# BackscatterPlantSensor_v2_test2.net
KiCad netlist of a schematic drawn in EAGLE
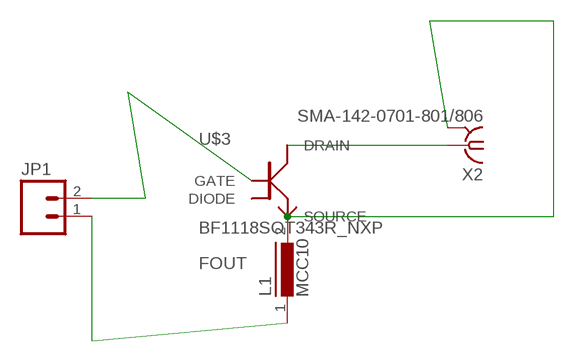
[diagram p0: schematic, sheet 1]

(export (version "E")
  (design (tool "Eeschema 10.0.6"))
  (components
    (comp (ref "JP1")
      (value "M02PTH")
      (footprint "eagle-import:1X02")
      (libsource (lib "eagle-import") (part "M02PTH"))
    )
    (comp (ref "L1")
      (value "MCC10")
      (footprint "eagle-import:MCC10")
      (libsource (lib "eagle-import") (part "MCC10"))
    )
    (comp (ref "U$3")
      (value "BF1118SOT343R_NXP")
      (footprint "eagle-import:SOT343R")
      (libsource (lib "eagle-import") (part "BF1118SOT343R_NXP"))
    )
    (comp (ref "X2")
      (value "SMA-142-0701-801/806")
      (footprint "eagle-import:J502-ND-142-0701-801_806")
      (fields (field (name "MF") "JOHNSON COMPONENTS") (field (name "MPN") "142-0701-801"))
      (libsource (lib "eagle-import") (part "SMA-142-0701-801/806"))
    )
  )
  (nets
    (net (code "1") (name "FOUT") (class "Default")
      (node (ref "JP1") (pin "1") (pinfunction "1_1") (pintype "passive"))
      (node (ref "L1") (pin "1") (pinfunction "1_1") (pintype "passive"))
    )
    (net (code "2") (name "Net-(U$3-DRAIN)") (class "Default")
      (node (ref "U$3") (pin "4") (pinfunction "DRAIN_4") (pintype "bidirectional"))
      (node (ref "X2") (pin "1") (pinfunction "1_1") (pintype "passive"))
    )
    (net (code "3") (name "Net-(U$3-GATE)") (class "Default")
      (node (ref "JP1") (pin "2") (pinfunction "2_2") (pintype "passive"))
      (node (ref "U$3") (pin "1") (pinfunction "GATE_1") (pintype "bidirectional"))
    )
    (net (code "4") (name "Net-(U$3-SOURCE)") (class "Default")
      (node (ref "L1") (pin "2") (pinfunction "2_2") (pintype "passive"))
      (node (ref "U$3") (pin "3") (pinfunction "SOURCE_3") (pintype "bidirectional"))
      (node (ref "X2") (pin "G@1") (pinfunction "GND_G@1") (pintype "power_in"))
    )
    (net (code "5") (name "unconnected-(U$3-DIODE-Pad2)") (class "Default")
      (node (ref "U$3") (pin "2") (pinfunction "DIODE_2") (pintype "bidirectional"))
    )
  )
)
